# 05_POWER-SUPPLY.net
KiCad netlist of a schematic drawn in Altium Designer
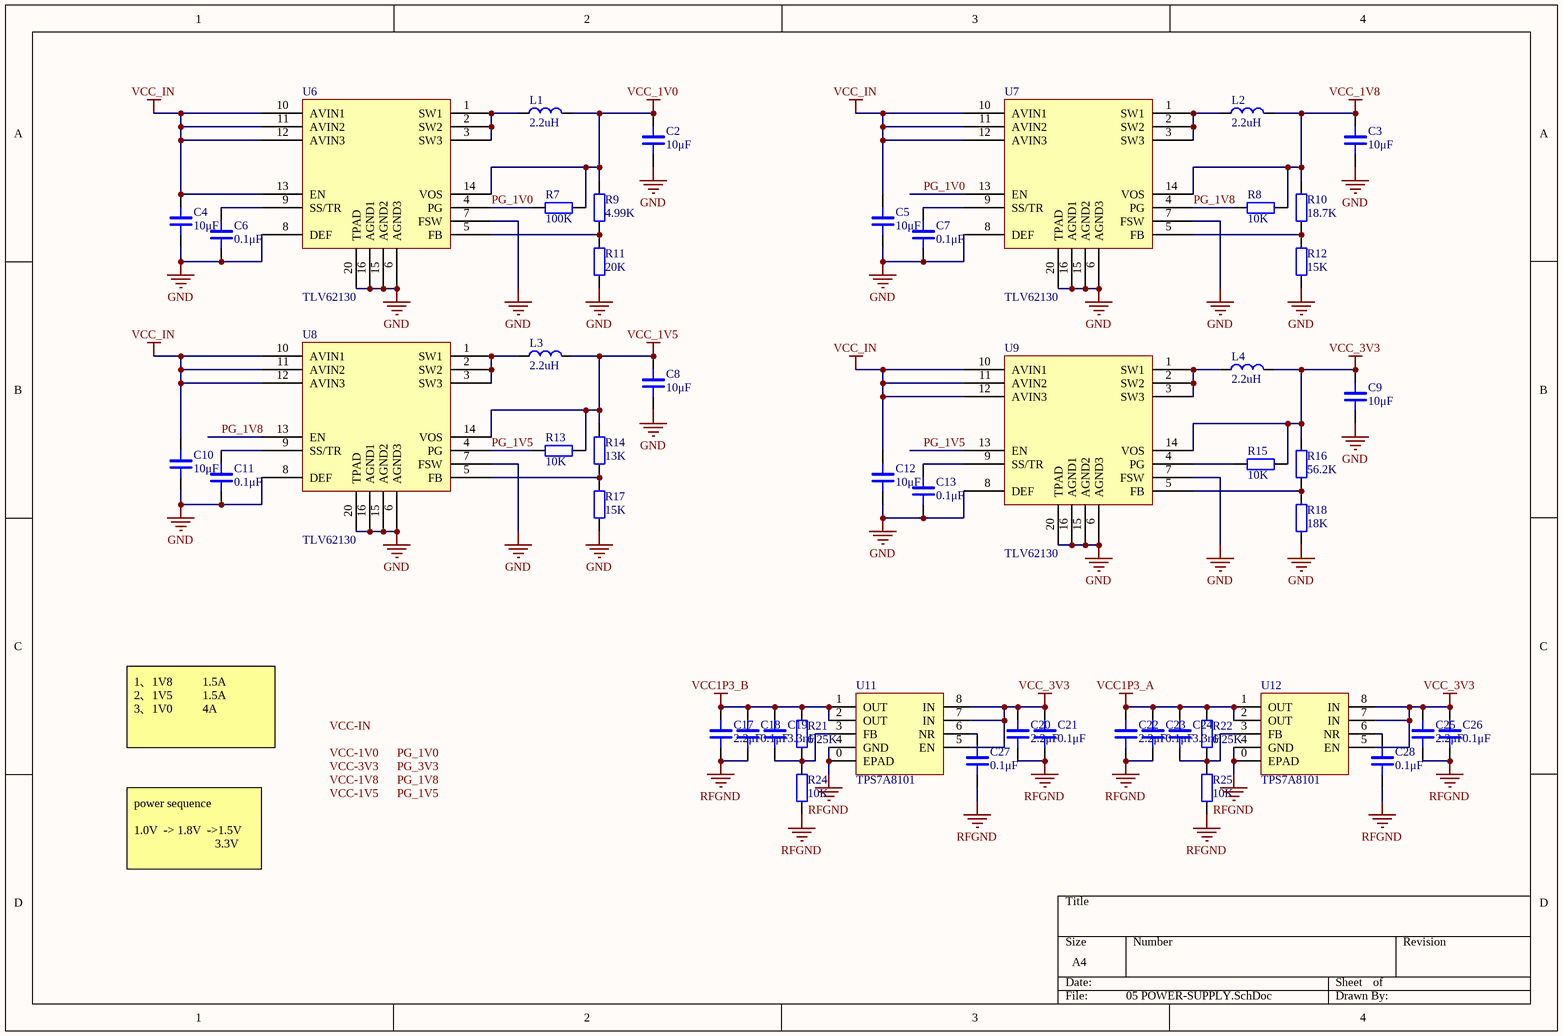
[diagram p0: 05 POWER-SUPPLY.SchDoc]

(export (version "E")
  (design (tool "Eeschema 10.0.6"))
  (components
    (comp (ref "C2")
      (value "10μF")
      (footprint "LC-0805_C")
      (description "Capacitor")
      (libsource (lib "NGFF_M_Key_xc7z010-clg400") (part "CAP_3"))
    )
    (comp (ref "C3")
      (value "10μF")
      (footprint "LC-0805_C")
      (description "Capacitor")
      (libsource (lib "NGFF_M_Key_xc7z010-clg400") (part "CAP_3"))
    )
    (comp (ref "C4")
      (value "10μF")
      (footprint "LC-0805_C")
      (description "Capacitor")
      (libsource (lib "NGFF_M_Key_xc7z010-clg400") (part "CAP_3"))
    )
    (comp (ref "C5")
      (value "10μF")
      (footprint "LC-0805_C")
      (description "Capacitor")
      (libsource (lib "NGFF_M_Key_xc7z010-clg400") (part "CAP_3"))
    )
    (comp (ref "C6")
      (value "0.1μF")
      (footprint "LC-0402_C")
      (description "Capacitor")
      (libsource (lib "NGFF_M_Key_xc7z010-clg400") (part "CAP_3"))
    )
    (comp (ref "C7")
      (value "0.1μF")
      (footprint "LC-0402_C")
      (description "Capacitor")
      (libsource (lib "NGFF_M_Key_xc7z010-clg400") (part "CAP_3"))
    )
    (comp (ref "C8")
      (value "10μF")
      (footprint "LC-0805_C")
      (description "Capacitor")
      (libsource (lib "NGFF_M_Key_xc7z010-clg400") (part "CAP_3"))
    )
    (comp (ref "C9")
      (value "10μF")
      (footprint "LC-0805_C")
      (description "Capacitor")
      (libsource (lib "NGFF_M_Key_xc7z010-clg400") (part "CAP_3"))
    )
    (comp (ref "C10")
      (value "10μF")
      (footprint "LC-0805_C")
      (description "Capacitor")
      (libsource (lib "NGFF_M_Key_xc7z010-clg400") (part "CAP_3"))
    )
    (comp (ref "C11")
      (value "0.1μF")
      (footprint "LC-0402_C")
      (description "Capacitor")
      (libsource (lib "NGFF_M_Key_xc7z010-clg400") (part "CAP_3"))
    )
    (comp (ref "C12")
      (value "10μF")
      (footprint "LC-0805_C")
      (description "Capacitor")
      (libsource (lib "NGFF_M_Key_xc7z010-clg400") (part "CAP_3"))
    )
    (comp (ref "C13")
      (value "0.1μF")
      (footprint "LC-0402_C")
      (description "Capacitor")
      (libsource (lib "NGFF_M_Key_xc7z010-clg400") (part "CAP_3"))
    )
    (comp (ref "C17")
      (value "2.2μF")
      (footprint "LC-0805_C")
      (description "Capacitor")
      (libsource (lib "NGFF_M_Key_xc7z010-clg400") (part "CAP_3"))
    )
    (comp (ref "C18")
      (value "0.1μF")
      (footprint "LC-0402_C")
      (description "Capacitor")
      (libsource (lib "NGFF_M_Key_xc7z010-clg400") (part "CAP_3"))
    )
    (comp (ref "C19")
      (value "3.3nF")
      (footprint "LC-0402_C")
      (description "Capacitor")
      (libsource (lib "NGFF_M_Key_xc7z010-clg400") (part "CAP_3"))
    )
    (comp (ref "C20")
      (value "2.2μF")
      (footprint "LC-0402_C")
      (description "Capacitor")
      (libsource (lib "NGFF_M_Key_xc7z010-clg400") (part "CAP_3"))
    )
    (comp (ref "C21")
      (value "0.1μF")
      (footprint "LC-0805_C")
      (description "Capacitor")
      (libsource (lib "NGFF_M_Key_xc7z010-clg400") (part "CAP_3"))
    )
    (comp (ref "C22")
      (value "2.2μF")
      (footprint "LC-0805_C")
      (description "Capacitor")
      (libsource (lib "NGFF_M_Key_xc7z010-clg400") (part "CAP_3"))
    )
    (comp (ref "C23")
      (value "0.1μF")
      (footprint "LC-0402_C")
      (description "Capacitor")
      (libsource (lib "NGFF_M_Key_xc7z010-clg400") (part "CAP_3"))
    )
    (comp (ref "C24")
      (value "3.3nF")
      (footprint "LC-0402_C")
      (description "Capacitor")
      (libsource (lib "NGFF_M_Key_xc7z010-clg400") (part "CAP_3"))
    )
    (comp (ref "C25")
      (value "2.2μF")
      (footprint "LC-0402_C")
      (description "Capacitor")
      (libsource (lib "NGFF_M_Key_xc7z010-clg400") (part "CAP_3"))
    )
    (comp (ref "C26")
      (value "0.1μF")
      (footprint "LC-0805_C")
      (description "Capacitor")
      (libsource (lib "NGFF_M_Key_xc7z010-clg400") (part "CAP_3"))
    )
    (comp (ref "C27")
      (value "0.1μF")
      (footprint "LC-0402_C")
      (description "Capacitor")
      (libsource (lib "NGFF_M_Key_xc7z010-clg400") (part "CAP_3"))
    )
    (comp (ref "C28")
      (value "0.1μF")
      (footprint "LC-0402_C")
      (description "Capacitor")
      (libsource (lib "NGFF_M_Key_xc7z010-clg400") (part "CAP_3"))
    )
    (comp (ref "L1")
      (value "2.2uH")
      (footprint "L1008")
      (description "Inductance")
      (libsource (lib "NGFF_M_Key_xc7z010-clg400") (part "INDUCTANCE_1"))
    )
    (comp (ref "L2")
      (value "2.2uH")
      (footprint "L1008")
      (description "Inductance")
      (libsource (lib "NGFF_M_Key_xc7z010-clg400") (part "INDUCTANCE_1"))
    )
    (comp (ref "L3")
      (value "2.2uH")
      (footprint "L1008")
      (description "Inductance")
      (libsource (lib "NGFF_M_Key_xc7z010-clg400") (part "INDUCTANCE_1"))
    )
    (comp (ref "L4")
      (value "2.2uH")
      (footprint "L1008")
      (description "Inductance")
      (libsource (lib "NGFF_M_Key_xc7z010-clg400") (part "INDUCTANCE_1"))
    )
    (comp (ref "R7")
      (value "100K")
      (footprint "LC-0402_R")
      (description "Resistor")
      (libsource (lib "") (part "RES_1"))
    )
    (comp (ref "R8")
      (value "10K")
      (footprint "LC-0402_R")
      (description "Resistor")
      (libsource (lib "") (part "RES_1"))
    )
    (comp (ref "R9")
      (value "4.99K")
      (footprint "LC-0402_R")
      (description "Resistor")
      (libsource (lib "NGFF_M_Key_xc7z010-clg400") (part "RES"))
    )
    (comp (ref "R10")
      (value "18.7K")
      (footprint "LC-0402_R")
      (description "Resistor")
      (libsource (lib "NGFF_M_Key_xc7z010-clg400") (part "RES"))
    )
    (comp (ref "R11")
      (value "20K")
      (footprint "LC-0402_R")
      (description "Resistor")
      (libsource (lib "NGFF_M_Key_xc7z010-clg400") (part "RES"))
    )
    (comp (ref "R12")
      (value "15K")
      (footprint "LC-0402_R")
      (description "Resistor")
      (libsource (lib "NGFF_M_Key_xc7z010-clg400") (part "RES"))
    )
    (comp (ref "R13")
      (value "10K")
      (footprint "LC-0402_R")
      (description "Resistor")
      (libsource (lib "") (part "RES_1"))
    )
    (comp (ref "R14")
      (value "13K")
      (footprint "LC-0402_R")
      (description "Resistor")
      (libsource (lib "NGFF_M_Key_xc7z010-clg400") (part "RES"))
    )
    (comp (ref "R15")
      (value "10K")
      (footprint "LC-0402_R")
      (description "Resistor")
      (libsource (lib "") (part "RES_1"))
    )
    (comp (ref "R16")
      (value "56.2K")
      (footprint "LC-0402_R")
      (description "Resistor")
      (libsource (lib "NGFF_M_Key_xc7z010-clg400") (part "RES"))
    )
    (comp (ref "R17")
      (value "15K")
      (footprint "LC-0402_R")
      (description "Resistor")
      (libsource (lib "NGFF_M_Key_xc7z010-clg400") (part "RES"))
    )
    (comp (ref "R18")
      (value "18K")
      (footprint "LC-0402_R")
      (description "Resistor")
      (libsource (lib "NGFF_M_Key_xc7z010-clg400") (part "RES"))
    )
    (comp (ref "R21")
      (value "6.25K")
      (footprint "LC-0402_R")
      (description "Resistor")
      (libsource (lib "NGFF_M_Key_xc7z010-clg400") (part "RES"))
    )
    (comp (ref "R22")
      (value "6.25K")
      (footprint "LC-0402_R")
      (description "Resistor")
      (libsource (lib "NGFF_M_Key_xc7z010-clg400") (part "RES"))
    )
    (comp (ref "R24")
      (value "10K")
      (footprint "LC-0402_R")
      (description "Resistor")
      (libsource (lib "NGFF_M_Key_xc7z010-clg400") (part "RES"))
    )
    (comp (ref "R25")
      (value "10K")
      (footprint "LC-0402_R")
      (description "Resistor")
      (libsource (lib "NGFF_M_Key_xc7z010-clg400") (part "RES"))
    )
    (comp (ref "U6")
      (value "TLV62130")
      (footprint "TLV62130RGT")
      (libsource (lib "PCB_Project") (part "TLV62130"))
    )
    (comp (ref "U7")
      (value "TLV62130")
      (footprint "TLV62130RGT")
      (libsource (lib "PCB_Project") (part "TLV62130"))
    )
    (comp (ref "U8")
      (value "TLV62130")
      (footprint "TLV62130RGT")
      (libsource (lib "PCB_Project") (part "TLV62130"))
    )
    (comp (ref "U9")
      (value "TLV62130")
      (footprint "TLV62130RGT")
      (libsource (lib "PCB_Project") (part "TLV62130"))
    )
    (comp (ref "U11")
      (value "TPS7A8101")
      (footprint "TPS7A8101")
      (libsource (lib "AD9363_ZYNQ_V2") (part "TPS7A8101"))
    )
    (comp (ref "U12")
      (value "TPS7A8101")
      (footprint "TPS7A8101")
      (libsource (lib "AD9363_ZYNQ_V2") (part "TPS7A8101"))
    )
  )
  (nets
    (net (code "1") (name "/PG_1V0") (class "Default")
      (node (ref "R7") (pin "2") (pinfunction "2_2") (pintype "passive"))
      (node (ref "U6") (pin "4") (pinfunction "PG_4") (pintype "passive"))
      (node (ref "U7") (pin "13") (pinfunction "EN_13") (pintype "passive"))
    )
    (net (code "2") (name "/PG_1V5") (class "Default")
      (node (ref "R13") (pin "2") (pinfunction "2_2") (pintype "passive"))
      (node (ref "U8") (pin "4") (pinfunction "PG_4") (pintype "passive"))
      (node (ref "U9") (pin "13") (pinfunction "EN_13") (pintype "passive"))
    )
    (net (code "3") (name "/PG_1V8") (class "Default")
      (node (ref "R8") (pin "2") (pinfunction "2_2") (pintype "passive"))
      (node (ref "U7") (pin "4") (pinfunction "PG_4") (pintype "passive"))
      (node (ref "U8") (pin "13") (pinfunction "EN_13") (pintype "passive"))
    )
    (net (code "10") (name "GND") (class "Default")
      (node (ref "C10") (pin "1") (pinfunction "1_1") (pintype "passive"))
      (node (ref "C11") (pin "1") (pinfunction "1_1") (pintype "passive"))
      (node (ref "C12") (pin "1") (pinfunction "1_1") (pintype "passive"))
      (node (ref "C13") (pin "1") (pinfunction "1_1") (pintype "passive"))
      (node (ref "C2") (pin "1") (pinfunction "1_1") (pintype "passive"))
      (node (ref "C3") (pin "1") (pinfunction "1_1") (pintype "passive"))
      (node (ref "C4") (pin "1") (pinfunction "1_1") (pintype "passive"))
      (node (ref "C5") (pin "1") (pinfunction "1_1") (pintype "passive"))
      (node (ref "C6") (pin "1") (pinfunction "1_1") (pintype "passive"))
      (node (ref "C7") (pin "1") (pinfunction "1_1") (pintype "passive"))
      (node (ref "C8") (pin "1") (pinfunction "1_1") (pintype "passive"))
      (node (ref "C9") (pin "1") (pinfunction "1_1") (pintype "passive"))
      (node (ref "R11") (pin "2") (pinfunction "2_2") (pintype "passive"))
      (node (ref "R12") (pin "2") (pinfunction "2_2") (pintype "passive"))
      (node (ref "R17") (pin "2") (pinfunction "2_2") (pintype "passive"))
      (node (ref "R18") (pin "2") (pinfunction "2_2") (pintype "passive"))
      (node (ref "U6") (pin "15") (pinfunction "AGND2_15") (pintype "passive"))
      (node (ref "U6") (pin "16") (pinfunction "AGND1_16") (pintype "passive"))
      (node (ref "U6") (pin "20") (pinfunction "TPAD_20") (pintype "passive"))
      (node (ref "U6") (pin "6") (pinfunction "AGND3_6") (pintype "passive"))
      (node (ref "U6") (pin "7") (pinfunction "FSW_7") (pintype "passive"))
      (node (ref "U6") (pin "8") (pinfunction "DEF_8") (pintype "passive"))
      (node (ref "U7") (pin "15") (pinfunction "AGND2_15") (pintype "passive"))
      (node (ref "U7") (pin "16") (pinfunction "AGND1_16") (pintype "passive"))
      (node (ref "U7") (pin "20") (pinfunction "TPAD_20") (pintype "passive"))
      (node (ref "U7") (pin "6") (pinfunction "AGND3_6") (pintype "passive"))
      (node (ref "U7") (pin "7") (pinfunction "FSW_7") (pintype "passive"))
      (node (ref "U7") (pin "8") (pinfunction "DEF_8") (pintype "passive"))
      (node (ref "U8") (pin "15") (pinfunction "AGND2_15") (pintype "passive"))
      (node (ref "U8") (pin "16") (pinfunction "AGND1_16") (pintype "passive"))
      (node (ref "U8") (pin "20") (pinfunction "TPAD_20") (pintype "passive"))
      (node (ref "U8") (pin "6") (pinfunction "AGND3_6") (pintype "passive"))
      (node (ref "U8") (pin "7") (pinfunction "FSW_7") (pintype "passive"))
      (node (ref "U8") (pin "8") (pinfunction "DEF_8") (pintype "passive"))
      (node (ref "U9") (pin "15") (pinfunction "AGND2_15") (pintype "passive"))
      (node (ref "U9") (pin "16") (pinfunction "AGND1_16") (pintype "passive"))
      (node (ref "U9") (pin "20") (pinfunction "TPAD_20") (pintype "passive"))
      (node (ref "U9") (pin "6") (pinfunction "AGND3_6") (pintype "passive"))
      (node (ref "U9") (pin "7") (pinfunction "FSW_7") (pintype "passive"))
      (node (ref "U9") (pin "8") (pinfunction "DEF_8") (pintype "passive"))
    )
    (net (code "11") (name "Net-(U6-FB)") (class "Default")
      (node (ref "R11") (pin "1") (pinfunction "1_1") (pintype "passive"))
      (node (ref "R9") (pin "2") (pinfunction "2_2") (pintype "passive"))
      (node (ref "U6") (pin "5") (pinfunction "FB_5") (pintype "passive"))
    )
    (net (code "12") (name "Net-(U6-SS{slash}TR)") (class "Default")
      (node (ref "C6") (pin "2") (pinfunction "2_2") (pintype "passive"))
      (node (ref "U6") (pin "9") (pinfunction "SS/TR_9") (pintype "passive"))
    )
    (net (code "13") (name "Net-(U6-SW1)") (class "Default")
      (node (ref "L1") (pin "1") (pinfunction "1_1") (pintype "passive"))
      (node (ref "U6") (pin "1") (pinfunction "SW1_1") (pintype "passive"))
      (node (ref "U6") (pin "2") (pinfunction "SW2_2") (pintype "passive"))
      (node (ref "U6") (pin "3") (pinfunction "SW3_3") (pintype "passive"))
    )
    (net (code "14") (name "Net-(U7-FB)") (class "Default")
      (node (ref "R10") (pin "2") (pinfunction "2_2") (pintype "passive"))
      (node (ref "R12") (pin "1") (pinfunction "1_1") (pintype "passive"))
      (node (ref "U7") (pin "5") (pinfunction "FB_5") (pintype "passive"))
    )
    (net (code "15") (name "Net-(U7-SS{slash}TR)") (class "Default")
      (node (ref "C7") (pin "2") (pinfunction "2_2") (pintype "passive"))
      (node (ref "U7") (pin "9") (pinfunction "SS/TR_9") (pintype "passive"))
    )
    (net (code "16") (name "Net-(U7-SW1)") (class "Default")
      (node (ref "L2") (pin "1") (pinfunction "1_1") (pintype "passive"))
      (node (ref "U7") (pin "1") (pinfunction "SW1_1") (pintype "passive"))
      (node (ref "U7") (pin "2") (pinfunction "SW2_2") (pintype "passive"))
      (node (ref "U7") (pin "3") (pinfunction "SW3_3") (pintype "passive"))
    )
    (net (code "17") (name "Net-(U8-FB)") (class "Default")
      (node (ref "R14") (pin "2") (pinfunction "2_2") (pintype "passive"))
      (node (ref "R17") (pin "1") (pinfunction "1_1") (pintype "passive"))
      (node (ref "U8") (pin "5") (pinfunction "FB_5") (pintype "passive"))
    )
    (net (code "18") (name "Net-(U8-SS{slash}TR)") (class "Default")
      (node (ref "C11") (pin "2") (pinfunction "2_2") (pintype "passive"))
      (node (ref "U8") (pin "9") (pinfunction "SS/TR_9") (pintype "passive"))
    )
    (net (code "19") (name "Net-(U8-SW1)") (class "Default")
      (node (ref "L3") (pin "1") (pinfunction "1_1") (pintype "passive"))
      (node (ref "U8") (pin "1") (pinfunction "SW1_1") (pintype "passive"))
      (node (ref "U8") (pin "2") (pinfunction "SW2_2") (pintype "passive"))
      (node (ref "U8") (pin "3") (pinfunction "SW3_3") (pintype "passive"))
    )
    (net (code "20") (name "Net-(U9-FB)") (class "Default")
      (node (ref "R16") (pin "2") (pinfunction "2_2") (pintype "passive"))
      (node (ref "R18") (pin "1") (pinfunction "1_1") (pintype "passive"))
      (node (ref "U9") (pin "5") (pinfunction "FB_5") (pintype "passive"))
    )
    (net (code "21") (name "Net-(U9-PG)") (class "Default")
      (node (ref "R15") (pin "2") (pinfunction "2_2") (pintype "passive"))
      (node (ref "U9") (pin "4") (pinfunction "PG_4") (pintype "passive"))
    )
    (net (code "22") (name "Net-(U9-SS{slash}TR)") (class "Default")
      (node (ref "C13") (pin "2") (pinfunction "2_2") (pintype "passive"))
      (node (ref "U9") (pin "9") (pinfunction "SS/TR_9") (pintype "passive"))
    )
    (net (code "23") (name "Net-(U9-SW1)") (class "Default")
      (node (ref "L4") (pin "1") (pinfunction "1_1") (pintype "passive"))
      (node (ref "U9") (pin "1") (pinfunction "SW1_1") (pintype "passive"))
      (node (ref "U9") (pin "2") (pinfunction "SW2_2") (pintype "passive"))
      (node (ref "U9") (pin "3") (pinfunction "SW3_3") (pintype "passive"))
    )
    (net (code "24") (name "Net-(U11-FB)") (class "Default")
      (node (ref "C19") (pin "1") (pinfunction "1_1") (pintype "passive"))
      (node (ref "R21") (pin "2") (pinfunction "2_2") (pintype "passive"))
      (node (ref "R24") (pin "1") (pinfunction "1_1") (pintype "passive"))
      (node (ref "U11") (pin "3") (pinfunction "FB_3") (pintype "passive"))
    )
    (net (code "25") (name "Net-(U11-NR)") (class "Default")
      (node (ref "C27") (pin "2") (pinfunction "2_2") (pintype "passive"))
      (node (ref "U11") (pin "6") (pinfunction "NR_6") (pintype "passive"))
    )
    (net (code "26") (name "Net-(U12-FB)") (class "Default")
      (node (ref "C24") (pin "1") (pinfunction "1_1") (pintype "passive"))
      (node (ref "R22") (pin "2") (pinfunction "2_2") (pintype "passive"))
      (node (ref "R25") (pin "1") (pinfunction "1_1") (pintype "passive"))
      (node (ref "U12") (pin "3") (pinfunction "FB_3") (pintype "passive"))
    )
    (net (code "27") (name "Net-(U12-NR)") (class "Default")
      (node (ref "C28") (pin "2") (pinfunction "2_2") (pintype "passive"))
      (node (ref "U12") (pin "6") (pinfunction "NR_6") (pintype "passive"))
    )
    (net (code "28") (name "RFGND") (class "Default")
      (node (ref "C17") (pin "1") (pinfunction "1_1") (pintype "passive"))
      (node (ref "C18") (pin "1") (pinfunction "1_1") (pintype "passive"))
      (node (ref "C20") (pin "1") (pinfunction "1_1") (pintype "passive"))
      (node (ref "C21") (pin "1") (pinfunction "1_1") (pintype "passive"))
      (node (ref "C22") (pin "1") (pinfunction "1_1") (pintype "passive"))
      (node (ref "C23") (pin "1") (pinfunction "1_1") (pintype "passive"))
      (node (ref "C25") (pin "1") (pinfunction "1_1") (pintype "passive"))
      (node (ref "C26") (pin "1") (pinfunction "1_1") (pintype "passive"))
      (node (ref "C27") (pin "1") (pinfunction "1_1") (pintype "passive"))
      (node (ref "C28") (pin "1") (pinfunction "1_1") (pintype "passive"))
      (node (ref "R24") (pin "2") (pinfunction "2_2") (pintype "passive"))
      (node (ref "R25") (pin "2") (pinfunction "2_2") (pintype "passive"))
      (node (ref "U11") (pin "0") (pinfunction "EPAD_0") (pintype "passive"))
      (node (ref "U11") (pin "4") (pinfunction "GND_4") (pintype "passive"))
      (node (ref "U12") (pin "0") (pinfunction "EPAD_0") (pintype "passive"))
      (node (ref "U12") (pin "4") (pinfunction "GND_4") (pintype "passive"))
    )
    (net (code "29") (name "VCC1P3_A") (class "Default")
      (node (ref "C22") (pin "2") (pinfunction "2_2") (pintype "passive"))
      (node (ref "C23") (pin "2") (pinfunction "2_2") (pintype "passive"))
      (node (ref "C24") (pin "2") (pinfunction "2_2") (pintype "passive"))
      (node (ref "R22") (pin "1") (pinfunction "1_1") (pintype "passive"))
      (node (ref "U12") (pin "1") (pinfunction "OUT_1") (pintype "passive"))
      (node (ref "U12") (pin "2") (pinfunction "OUT_2") (pintype "passive"))
    )
    (net (code "30") (name "VCC1P3_B") (class "Default")
      (node (ref "C17") (pin "2") (pinfunction "2_2") (pintype "passive"))
      (node (ref "C18") (pin "2") (pinfunction "2_2") (pintype "passive"))
      (node (ref "C19") (pin "2") (pinfunction "2_2") (pintype "passive"))
      (node (ref "R21") (pin "1") (pinfunction "1_1") (pintype "passive"))
      (node (ref "U11") (pin "1") (pinfunction "OUT_1") (pintype "passive"))
      (node (ref "U11") (pin "2") (pinfunction "OUT_2") (pintype "passive"))
    )
    (net (code "31") (name "VCC_1V0") (class "Default")
      (node (ref "C2") (pin "2") (pinfunction "2_2") (pintype "passive"))
      (node (ref "L1") (pin "2") (pinfunction "2_2") (pintype "passive"))
      (node (ref "R7") (pin "1") (pinfunction "1_1") (pintype "passive"))
      (node (ref "R9") (pin "1") (pinfunction "1_1") (pintype "passive"))
      (node (ref "U6") (pin "14") (pinfunction "VOS_14") (pintype "passive"))
    )
    (net (code "32") (name "VCC_1V5") (class "Default")
      (node (ref "C8") (pin "2") (pinfunction "2_2") (pintype "passive"))
      (node (ref "L3") (pin "2") (pinfunction "2_2") (pintype "passive"))
      (node (ref "R13") (pin "1") (pinfunction "1_1") (pintype "passive"))
      (node (ref "R14") (pin "1") (pinfunction "1_1") (pintype "passive"))
      (node (ref "U8") (pin "14") (pinfunction "VOS_14") (pintype "passive"))
    )
    (net (code "33") (name "VCC_1V8") (class "Default")
      (node (ref "C3") (pin "2") (pinfunction "2_2") (pintype "passive"))
      (node (ref "L2") (pin "2") (pinfunction "2_2") (pintype "passive"))
      (node (ref "R10") (pin "1") (pinfunction "1_1") (pintype "passive"))
      (node (ref "R8") (pin "1") (pinfunction "1_1") (pintype "passive"))
      (node (ref "U7") (pin "14") (pinfunction "VOS_14") (pintype "passive"))
    )
    (net (code "34") (name "VCC_3V3") (class "Default")
      (node (ref "C20") (pin "2") (pinfunction "2_2") (pintype "passive"))
      (node (ref "C21") (pin "2") (pinfunction "2_2") (pintype "passive"))
      (node (ref "C25") (pin "2") (pinfunction "2_2") (pintype "passive"))
      (node (ref "C26") (pin "2") (pinfunction "2_2") (pintype "passive"))
      (node (ref "C9") (pin "2") (pinfunction "2_2") (pintype "passive"))
      (node (ref "L4") (pin "2") (pinfunction "2_2") (pintype "passive"))
      (node (ref "R15") (pin "1") (pinfunction "1_1") (pintype "passive"))
      (node (ref "R16") (pin "1") (pinfunction "1_1") (pintype "passive"))
      (node (ref "U11") (pin "5") (pinfunction "EN_5") (pintype "passive"))
      (node (ref "U11") (pin "7") (pinfunction "IN_7") (pintype "passive"))
      (node (ref "U11") (pin "8") (pinfunction "IN_8") (pintype "passive"))
      (node (ref "U12") (pin "5") (pinfunction "EN_5") (pintype "passive"))
      (node (ref "U12") (pin "7") (pinfunction "IN_7") (pintype "passive"))
      (node (ref "U12") (pin "8") (pinfunction "IN_8") (pintype "passive"))
      (node (ref "U9") (pin "14") (pinfunction "VOS_14") (pintype "passive"))
    )
    (net (code "35") (name "VCC_IN") (class "Default")
      (node (ref "C10") (pin "2") (pinfunction "2_2") (pintype "passive"))
      (node (ref "C12") (pin "2") (pinfunction "2_2") (pintype "passive"))
      (node (ref "C4") (pin "2") (pinfunction "2_2") (pintype "passive"))
      (node (ref "C5") (pin "2") (pinfunction "2_2") (pintype "passive"))
      (node (ref "U6") (pin "10") (pinfunction "AVIN1_10") (pintype "passive"))
      (node (ref "U6") (pin "11") (pinfunction "AVIN2_11") (pintype "passive"))
      (node (ref "U6") (pin "12") (pinfunction "AVIN3_12") (pintype "passive"))
      (node (ref "U6") (pin "13") (pinfunction "EN_13") (pintype "passive"))
      (node (ref "U7") (pin "10") (pinfunction "AVIN1_10") (pintype "passive"))
      (node (ref "U7") (pin "11") (pinfunction "AVIN2_11") (pintype "passive"))
      (node (ref "U7") (pin "12") (pinfunction "AVIN3_12") (pintype "passive"))
      (node (ref "U8") (pin "10") (pinfunction "AVIN1_10") (pintype "passive"))
      (node (ref "U8") (pin "11") (pinfunction "AVIN2_11") (pintype "passive"))
      (node (ref "U8") (pin "12") (pinfunction "AVIN3_12") (pintype "passive"))
      (node (ref "U9") (pin "10") (pinfunction "AVIN1_10") (pintype "passive"))
      (node (ref "U9") (pin "11") (pinfunction "AVIN2_11") (pintype "passive"))
      (node (ref "U9") (pin "12") (pinfunction "AVIN3_12") (pintype "passive"))
    )
  )
)
